# Schematic.net
KiCad netlist of a schematic drawn in EAGLE
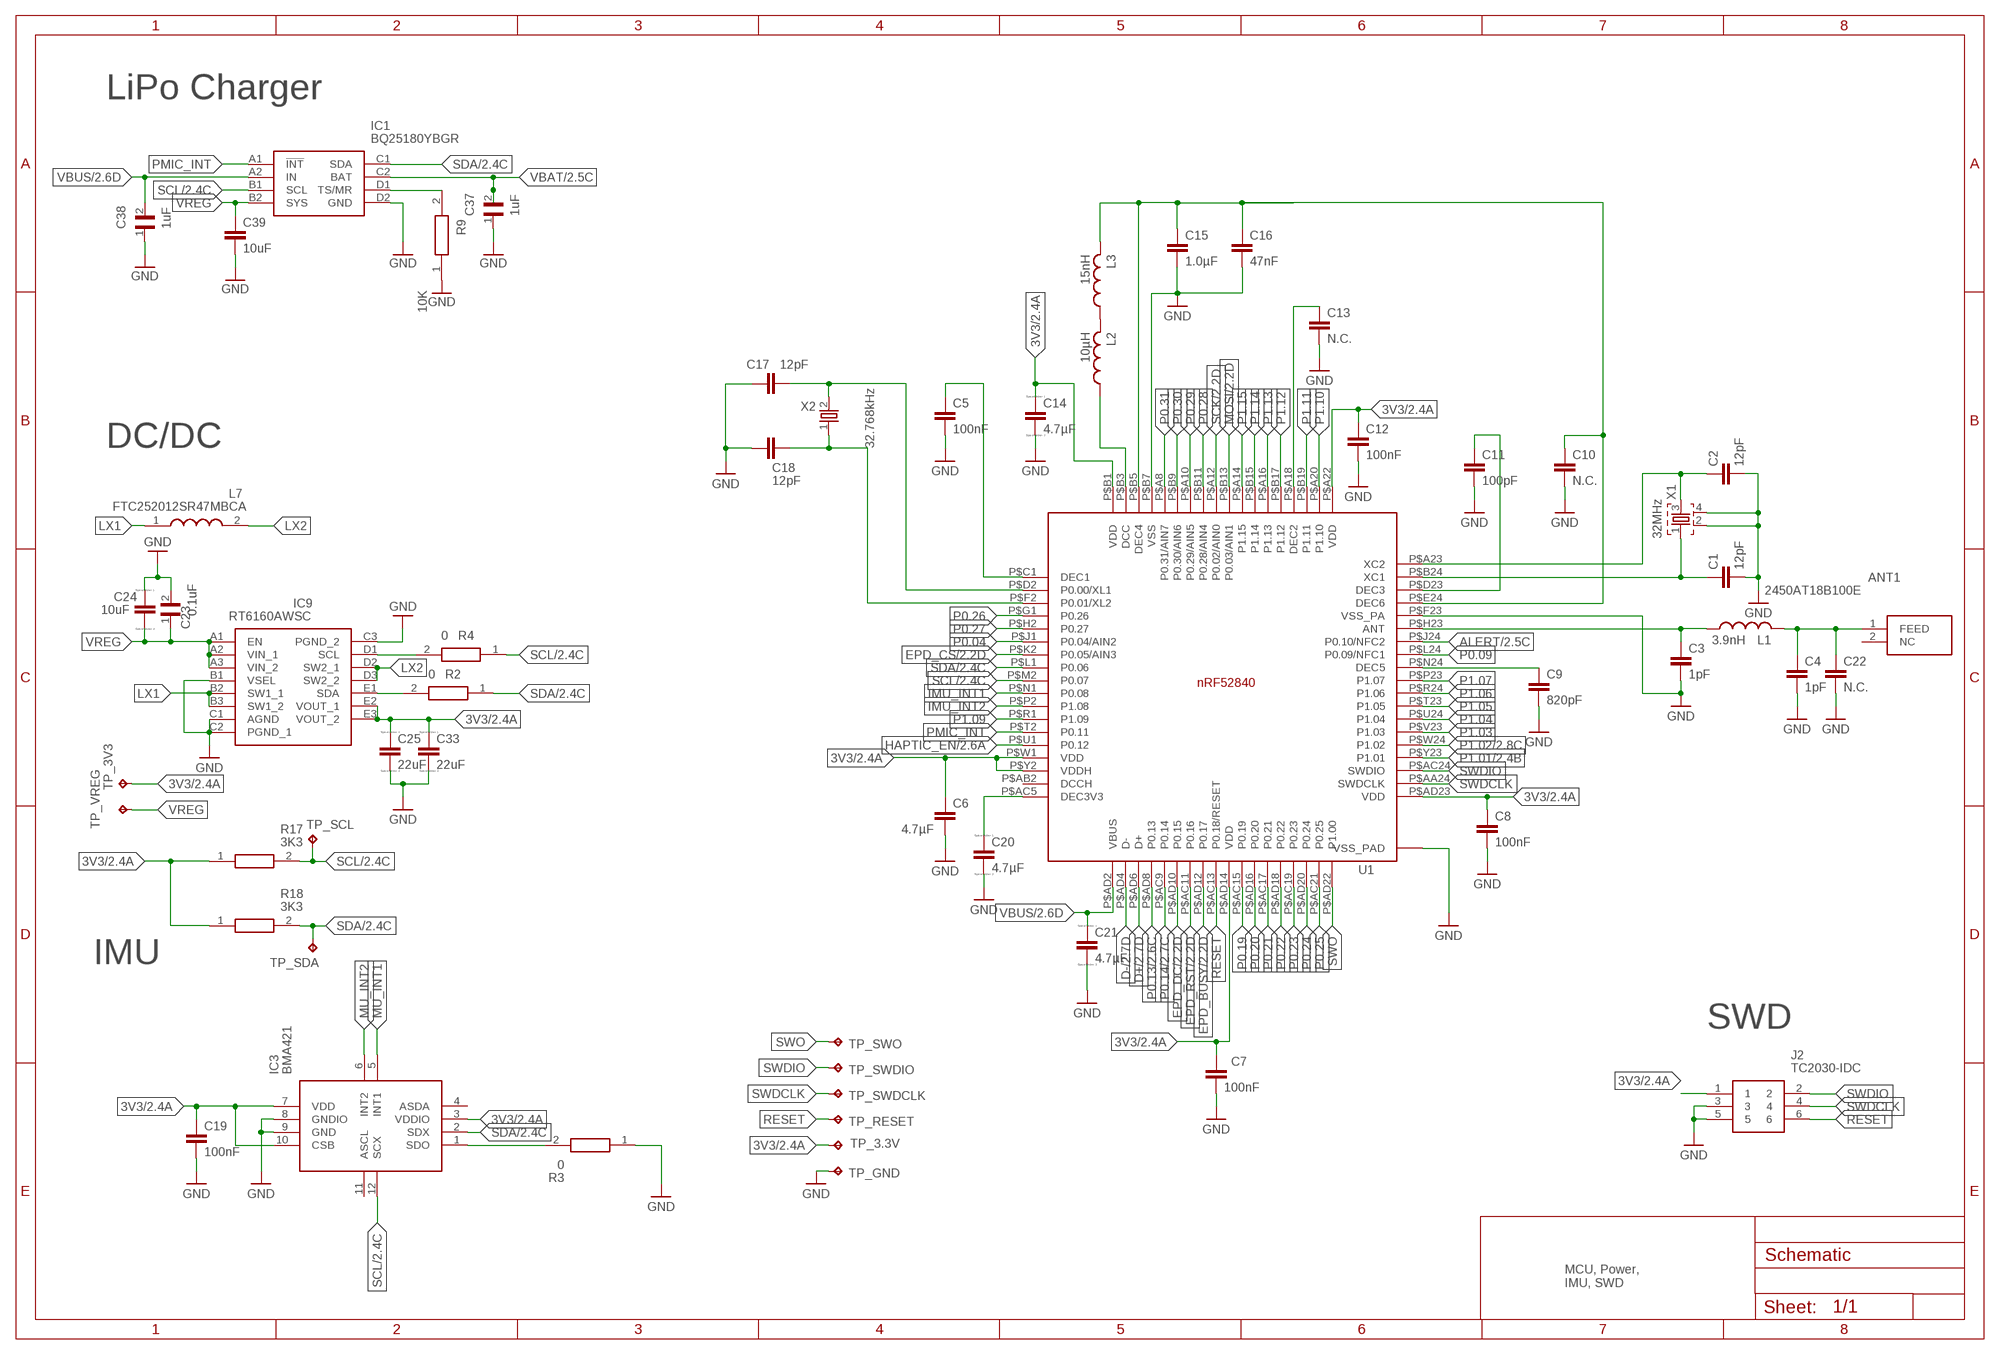
[diagram p0: schematic, sheet 1, part 1 of 2]
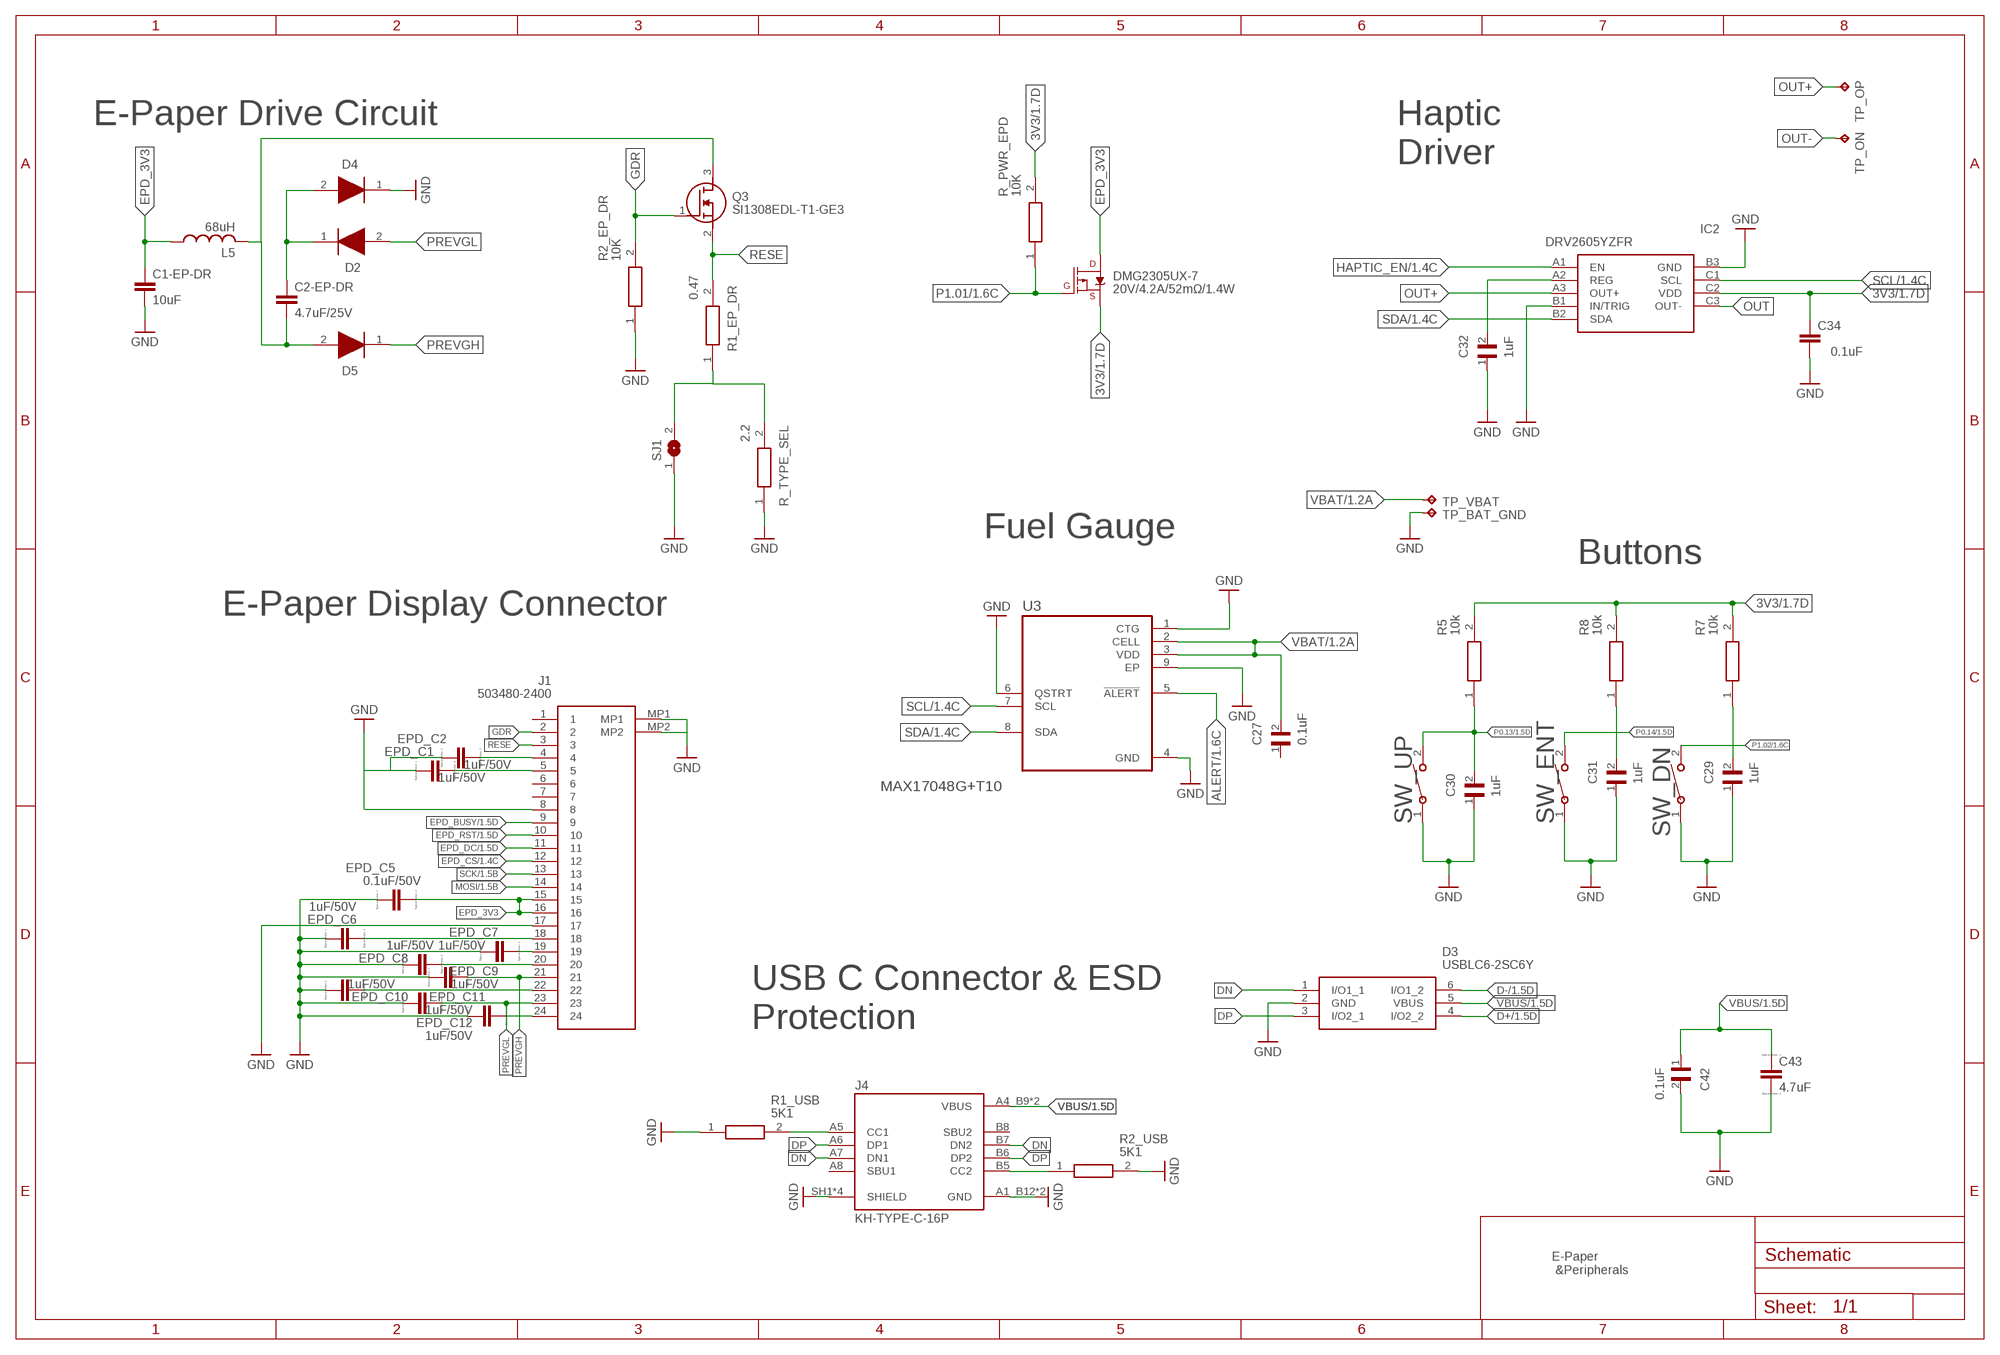
[diagram p1: schematic, sheet 1, part 2 of 2]

(export (version "E")
  (design (tool "Eeschema 10.0.6"))
  (components
    (comp (ref "ANT1")
      (value "2450AT18B100E")
      (footprint "eagle-import:2450AT18B100E_ANTC3216X140N")
      (fields (field (name "MOUSER_PART_NUMBER") "609-2450AT18B100E"))
      (libsource (lib "eagle-import") (part "2450AT18B100E_2450AT18B100E"))
    )
    (comp (ref "C1")
      (value "12pF")
      (footprint "eagle-import:NORDIC_NRF_3_RESC0201_L")
      (libsource (lib "eagle-import") (part "NORDIC_NRF_3_CAPACITOR_0201_L"))
    )
    (comp (ref "C1-EP-DR")
      (value "10uF")
      (footprint "eagle-import:NORDIC_NRF_3_RESC0201_L")
      (libsource (lib "eagle-import") (part "NORDIC_NRF_3_CAPACITOR_0201_L"))
    )
    (comp (ref "C2")
      (value "12pF")
      (footprint "eagle-import:NORDIC_NRF_3_RESC0201_L")
      (libsource (lib "eagle-import") (part "NORDIC_NRF_3_CAPACITOR_0201_L"))
    )
    (comp (ref "C2-EP-DR")
      (value "4.7uF/25V")
      (footprint "eagle-import:NORDIC_NRF_3_RESC0201_L")
      (libsource (lib "eagle-import") (part "NORDIC_NRF_3_CAPACITOR_0201_L"))
    )
    (comp (ref "C3")
      (value "1pF")
      (footprint "eagle-import:NORDIC_NRF_3_RESC0201_L")
      (libsource (lib "eagle-import") (part "NORDIC_NRF_3_CAPACITOR_0201_L"))
    )
    (comp (ref "C4")
      (value "1pF")
      (footprint "eagle-import:NORDIC_NRF_3_RESC0201_L")
      (libsource (lib "eagle-import") (part "NORDIC_NRF_3_CAPACITOR_0201_L"))
    )
    (comp (ref "C5")
      (value "100nF")
      (footprint "eagle-import:NORDIC_NRF_3_RESC0201_L")
      (libsource (lib "eagle-import") (part "NORDIC_NRF_3_CAPACITOR_0201_L"))
    )
    (comp (ref "C6")
      (value "4.7µF")
      (footprint "eagle-import:NORDIC_NRF_3_RESC0201_L")
      (libsource (lib "eagle-import") (part "NORDIC_NRF_3_CAPACITOR_0201_L"))
    )
    (comp (ref "C7")
      (value "100nF")
      (footprint "eagle-import:NORDIC_NRF_3_RESC0201_L")
      (libsource (lib "eagle-import") (part "NORDIC_NRF_3_CAPACITOR_0201_L"))
    )
    (comp (ref "C8")
      (value "100nF")
      (footprint "eagle-import:NORDIC_NRF_3_RESC0201_L")
      (libsource (lib "eagle-import") (part "NORDIC_NRF_3_CAPACITOR_0201_L"))
    )
    (comp (ref "C9")
      (value "820pF")
      (footprint "eagle-import:NORDIC_NRF_3_RESC0201_L")
      (libsource (lib "eagle-import") (part "NORDIC_NRF_3_CAPACITOR_0201_L"))
    )
    (comp (ref "C10")
      (value "N.C.")
      (footprint "eagle-import:NORDIC_NRF_3_RESC0201_L")
      (libsource (lib "eagle-import") (part "NORDIC_NRF_3_CAPACITOR_0201_L"))
    )
    (comp (ref "C11")
      (value "100pF")
      (footprint "eagle-import:NORDIC_NRF_3_RESC0201_L")
      (libsource (lib "eagle-import") (part "NORDIC_NRF_3_CAPACITOR_0201_L"))
    )
    (comp (ref "C12")
      (value "100nF")
      (footprint "eagle-import:NORDIC_NRF_3_RESC0201_L")
      (libsource (lib "eagle-import") (part "NORDIC_NRF_3_CAPACITOR_0201_L"))
    )
    (comp (ref "C13")
      (value "N.C.")
      (footprint "eagle-import:NORDIC_NRF_3_RESC0201_L")
      (libsource (lib "eagle-import") (part "NORDIC_NRF_3_CAPACITOR_0201_L"))
    )
    (comp (ref "C14")
      (value "4.7µF")
      (footprint "eagle-import:ESP32_C6_LIBRARY_1_ESP32_WROVER_EAGLE-LTSPICE_C0402")
      (libsource (lib "eagle-import") (part "ESP32_C6_LIBRARY_1_ESP32_WROVER_EAGLE-LTSPICE_CC0402"))
    )
    (comp (ref "C15")
      (value "1.0µF")
      (footprint "eagle-import:NORDIC_NRF_3_RESC0201_L")
      (libsource (lib "eagle-import") (part "NORDIC_NRF_3_CAPACITOR_0201_L"))
    )
    (comp (ref "C16")
      (value "47nF")
      (footprint "eagle-import:NORDIC_NRF_3_RESC0201_L")
      (libsource (lib "eagle-import") (part "NORDIC_NRF_3_CAPACITOR_0201_L"))
    )
    (comp (ref "C17")
      (value "12pF")
      (footprint "eagle-import:NORDIC_NRF_3_RESC0201_L")
      (libsource (lib "eagle-import") (part "NORDIC_NRF_3_CAPACITOR_0201_L"))
    )
    (comp (ref "C18")
      (value "12pF")
      (footprint "eagle-import:NORDIC_NRF_3_RESC0201_L")
      (libsource (lib "eagle-import") (part "NORDIC_NRF_3_CAPACITOR_0201_L"))
    )
    (comp (ref "C19")
      (value "100nF")
      (footprint "eagle-import:NORDIC_NRF_3_RESC0201_L")
      (libsource (lib "eagle-import") (part "NORDIC_NRF_3_CAPACITOR_0201_L"))
    )
    (comp (ref "C20")
      (value "4.7µF")
      (footprint "eagle-import:ESP32_C6_LIBRARY_1_ESP32_WROVER_EAGLE-LTSPICE_C0402")
      (libsource (lib "eagle-import") (part "ESP32_C6_LIBRARY_1_ESP32_WROVER_EAGLE-LTSPICE_CC0402"))
    )
    (comp (ref "C21")
      (value "4.7µF")
      (footprint "eagle-import:ESP32_C6_LIBRARY_1_ESP32_WROVER_EAGLE-LTSPICE_C0402")
      (libsource (lib "eagle-import") (part "ESP32_C6_LIBRARY_1_ESP32_WROVER_EAGLE-LTSPICE_CC0402"))
    )
    (comp (ref "C22")
      (value "N.C.")
      (footprint "eagle-import:NORDIC_NRF_3_RESC0201_L")
      (libsource (lib "eagle-import") (part "NORDIC_NRF_3_CAPACITOR_0201_L"))
    )
    (comp (ref "C23")
      (value "0.1uF")
      (footprint "eagle-import:GRM011R60J152KE01L_2_CAPC0201X13N")
      (fields (field (name "MF") "Murata") (field (name "MP") "GRM011R60J152KE01L"))
      (libsource (lib "eagle-import") (part "GRM011R60J152KE01L_2_GRM011R60J152KE01L"))
    )
    (comp (ref "C24")
      (value "10uF")
      (footprint "eagle-import:ESP32_C6_LIBRARY_1_ESP32_WROVER_EAGLE-LTSPICE_C0402")
      (libsource (lib "eagle-import") (part "ESP32_C6_LIBRARY_1_ESP32_WROVER_EAGLE-LTSPICE_CC0402"))
    )
    (comp (ref "C25")
      (value "22uF")
      (footprint "eagle-import:ESP32_C6_LIBRARY_1_ESP32_WROVER_EAGLE-LTSPICE_C0402")
      (libsource (lib "eagle-import") (part "ESP32_C6_LIBRARY_1_ESP32_WROVER_EAGLE-LTSPICE_CC0402"))
    )
    (comp (ref "C27")
      (value "0.1uF")
      (footprint "eagle-import:GRM011R60J152KE01L_2_CAPC0201X13N")
      (fields (field (name "MF") "Murata") (field (name "MP") "GRM011R60J152KE01L"))
      (libsource (lib "eagle-import") (part "GRM011R60J152KE01L_2_GRM011R60J152KE01L"))
    )
    (comp (ref "C29")
      (value "1uF")
      (footprint "eagle-import:GRM011R60J152KE01L_2_CAPC0201X13N")
      (fields (field (name "MF") "Murata") (field (name "MP") "GRM011R60J152KE01L"))
      (libsource (lib "eagle-import") (part "GRM011R60J152KE01L_2_GRM011R60J152KE01L"))
    )
    (comp (ref "C30")
      (value "1uF")
      (footprint "eagle-import:GRM011R60J152KE01L_2_CAPC0201X13N")
      (fields (field (name "MF") "Murata") (field (name "MP") "GRM011R60J152KE01L"))
      (libsource (lib "eagle-import") (part "GRM011R60J152KE01L_2_GRM011R60J152KE01L"))
    )
    (comp (ref "C31")
      (value "1uF")
      (footprint "eagle-import:GRM011R60J152KE01L_2_CAPC0201X13N")
      (fields (field (name "MF") "Murata") (field (name "MP") "GRM011R60J152KE01L"))
      (libsource (lib "eagle-import") (part "GRM011R60J152KE01L_2_GRM011R60J152KE01L"))
    )
    (comp (ref "C32")
      (value "1uF")
      (footprint "eagle-import:GRM011R60J152KE01L_2_CAPC0201X13N")
      (fields (field (name "MF") "Murata") (field (name "MP") "GRM011R60J152KE01L"))
      (libsource (lib "eagle-import") (part "GRM011R60J152KE01L_2_GRM011R60J152KE01L"))
    )
    (comp (ref "C33")
      (value "22uF")
      (footprint "eagle-import:ESP32_C6_LIBRARY_1_ESP32_WROVER_EAGLE-LTSPICE_C0402")
      (libsource (lib "eagle-import") (part "ESP32_C6_LIBRARY_1_ESP32_WROVER_EAGLE-LTSPICE_CC0402"))
    )
    (comp (ref "C34")
      (value "0.1uF")
      (footprint "eagle-import:NORDIC_NRF_3_RESC0201_L")
      (libsource (lib "eagle-import") (part "NORDIC_NRF_3_CAPACITOR_0201_L"))
    )
    (comp (ref "C37")
      (value "1uF")
      (footprint "eagle-import:GRM011R60J152KE01L_2_CAPC0201X13N")
      (fields (field (name "MF") "Murata") (field (name "MP") "GRM011R60J152KE01L"))
      (libsource (lib "eagle-import") (part "GRM011R60J152KE01L_2_GRM011R60J152KE01L"))
    )
    (comp (ref "C38")
      (value "1uF")
      (footprint "eagle-import:GRM011R60J152KE01L_2_CAPC0201X13N")
      (fields (field (name "MF") "Murata") (field (name "MP") "GRM011R60J152KE01L"))
      (libsource (lib "eagle-import") (part "GRM011R60J152KE01L_2_GRM011R60J152KE01L"))
    )
    (comp (ref "C39")
      (value "10uF")
      (footprint "eagle-import:NORDIC_NRF_3_RESC0201_L")
      (libsource (lib "eagle-import") (part "NORDIC_NRF_3_CAPACITOR_0201_L"))
    )
    (comp (ref "C42")
      (value "0.1uF")
      (footprint "eagle-import:GRM011R60J152KE01L_2_CAPC0201X13N")
      (fields (field (name "MF") "Murata") (field (name "MP") "GRM011R60J152KE01L"))
      (libsource (lib "eagle-import") (part "GRM011R60J152KE01L_2_GRM011R60J152KE01L"))
    )
    (comp (ref "C43")
      (value "4.7uF")
      (footprint "eagle-import:ESP32_C6_LIBRARY_1_ESP32_WROVER_EAGLE-LTSPICE_C0402")
      (libsource (lib "eagle-import") (part "ESP32_C6_LIBRARY_1_ESP32_WROVER_EAGLE-LTSPICE_CC0402"))
    )
    (comp (ref "D2")
      (value "ESP32_C6_LIBRARY_5_MBR0530")
      (footprint "eagle-import:ESP32_C6_LIBRARY_5_SOD3716X135N")
      (fields (field (name "MF") "ON Semiconductor") (field (name "MP") "MBR0530"))
      (libsource (lib "eagle-import") (part "ESP32_C6_LIBRARY_5_MBR0530"))
    )
    (comp (ref "D3")
      (value "USBLC6-2SC6Y")
      (footprint "eagle-import:ESP32_C6_LIBRARY_3_SOT95P280X145-6N")
      (fields (field (name "MF") "STMicroelectronics"))
      (libsource (lib "eagle-import") (part "ESP32_C6_LIBRARY_3_USBLC6-2SC6Y"))
    )
    (comp (ref "D4")
      (value "ESP32_C6_LIBRARY_5_MBR0530")
      (footprint "eagle-import:ESP32_C6_LIBRARY_5_SOD3716X135N")
      (fields (field (name "MF") "ON Semiconductor") (field (name "MP") "MBR0530"))
      (libsource (lib "eagle-import") (part "ESP32_C6_LIBRARY_5_MBR0530"))
    )
    (comp (ref "D5")
      (value "ESP32_C6_LIBRARY_5_MBR0530")
      (footprint "eagle-import:ESP32_C6_LIBRARY_5_SOD3716X135N")
      (fields (field (name "MF") "ON Semiconductor") (field (name "MP") "MBR0530"))
      (libsource (lib "eagle-import") (part "ESP32_C6_LIBRARY_5_MBR0530"))
    )
    (comp (ref "DMG2305UX-7")
      (value "20V/4.2A/52mΩ/1.4W")
      (footprint "eagle-import:ESP32_C6_LIBRARY_4_ESP32_C6_LIBRARY_4_ESP32_C6_LIBRARY_4_ESP32_C6_LIBRARY_4_ESP32_WROVER_SPARKFUN-DISCRETESEMI_SOT23-3")
      (libsource (lib "eagle-import") (part "ESP32_C6_LIBRARY_4_ESP32_WROVER_SPARKFUN-DISCRETESEMI_MOSFET_PCH-DMG2305UX-7"))
    )
    (comp (ref "EPD_C1")
      (value "1uF/50V")
      (footprint "eagle-import:ESP32_C6_LIBRARY_1_ESP32_WROVER_EAGLE-LTSPICE_C0402")
      (libsource (lib "eagle-import") (part "ESP32_C6_LIBRARY_1_ESP32_WROVER_EAGLE-LTSPICE_CC0402"))
    )
    (comp (ref "EPD_C2")
      (value "1uF/50V")
      (footprint "eagle-import:ESP32_C6_LIBRARY_1_ESP32_WROVER_EAGLE-LTSPICE_C0402")
      (libsource (lib "eagle-import") (part "ESP32_C6_LIBRARY_1_ESP32_WROVER_EAGLE-LTSPICE_CC0402"))
    )
    (comp (ref "EPD_C5")
      (value "0.1uF/50V")
      (footprint "eagle-import:ESP32_C6_LIBRARY_1_ESP32_WROVER_EAGLE-LTSPICE_C0402")
      (libsource (lib "eagle-import") (part "ESP32_C6_LIBRARY_1_ESP32_WROVER_EAGLE-LTSPICE_CC0402"))
    )
    (comp (ref "EPD_C6")
      (value "1uF/50V")
      (footprint "eagle-import:ESP32_C6_LIBRARY_1_ESP32_WROVER_EAGLE-LTSPICE_C0402")
      (libsource (lib "eagle-import") (part "ESP32_C6_LIBRARY_1_ESP32_WROVER_EAGLE-LTSPICE_CC0402"))
    )
    (comp (ref "EPD_C7")
      (value "1uF/50V")
      (footprint "eagle-import:ESP32_C6_LIBRARY_1_ESP32_WROVER_EAGLE-LTSPICE_C0402")
      (libsource (lib "eagle-import") (part "ESP32_C6_LIBRARY_1_ESP32_WROVER_EAGLE-LTSPICE_CC0402"))
    )
    (comp (ref "EPD_C8")
      (value "1uF/50V")
      (footprint "eagle-import:ESP32_C6_LIBRARY_1_ESP32_WROVER_EAGLE-LTSPICE_C0402")
      (libsource (lib "eagle-import") (part "ESP32_C6_LIBRARY_1_ESP32_WROVER_EAGLE-LTSPICE_CC0402"))
    )
    (comp (ref "EPD_C9")
      (value "1uF/50V")
      (footprint "eagle-import:ESP32_C6_LIBRARY_1_ESP32_WROVER_EAGLE-LTSPICE_C0402")
      (libsource (lib "eagle-import") (part "ESP32_C6_LIBRARY_1_ESP32_WROVER_EAGLE-LTSPICE_CC0402"))
    )
    (comp (ref "EPD_C10")
      (value "1uF/50V")
      (footprint "eagle-import:ESP32_C6_LIBRARY_1_ESP32_WROVER_EAGLE-LTSPICE_C0402")
      (libsource (lib "eagle-import") (part "ESP32_C6_LIBRARY_1_ESP32_WROVER_EAGLE-LTSPICE_CC0402"))
    )
    (comp (ref "EPD_C11")
      (value "1uF/50V")
      (footprint "eagle-import:ESP32_C6_LIBRARY_1_ESP32_WROVER_EAGLE-LTSPICE_C0402")
      (libsource (lib "eagle-import") (part "ESP32_C6_LIBRARY_1_ESP32_WROVER_EAGLE-LTSPICE_CC0402"))
    )
    (comp (ref "EPD_C12")
      (value "1uF/50V")
      (footprint "eagle-import:ESP32_C6_LIBRARY_1_ESP32_WROVER_EAGLE-LTSPICE_C0402")
      (libsource (lib "eagle-import") (part "ESP32_C6_LIBRARY_1_ESP32_WROVER_EAGLE-LTSPICE_CC0402"))
    )
    (comp (ref "IC1")
      (value "BQ25180YBGR")
      (footprint "eagle-import:BQ25180YBGR_BGA8C40P2X4_100X155X50")
      (fields (field (name "MOUSER_PART_NUMBER") "595-BQ25180YBGR"))
      (libsource (lib "eagle-import") (part "BQ25180YBGR_BQ25180YBGR"))
    )
    (comp (ref "IC2")
      (value "DRV2605YZFR")
      (footprint "eagle-import:DRV2605YZFR_BGA9C50P3X3_144X144X62")
      (libsource (lib "eagle-import") (part "DRV2605YZFR_DRV2605YZFR"))
    )
    (comp (ref "IC3")
      (value "BMA421")
      (footprint "eagle-import:BMA423_BMA423")
      (fields (field (name "ARROW_PART_NUMBER") "BMA423") (field (name "MOUSER_PART_NUMBER") "262-BMA423"))
      (libsource (lib "eagle-import") (part "BMA423_BMA423"))
    )
    (comp (ref "IC9")
      (value "RT6160AWSC")
      (footprint "eagle-import:RT6160AWSC_BGA15C40P3X5_140X230X60")
      (fields (field (name "MOUSER_PART_NUMBER") "835-RT6160AWSC"))
      (libsource (lib "eagle-import") (part "RT6160AWSC_RT6160AWSC"))
    )
    (comp (ref "J1")
      (value "503480-2400")
      (footprint "eagle-import:503480-2400_5034802400")
      (fields (field (name "MOUSER_PART_NUMBER") "538-503480-2400"))
      (libsource (lib "eagle-import") (part "503480-2400_503480-2400"))
    )
    (comp (ref "J2")
      (value "TC2030-IDC")
      (footprint "eagle-import:TC2030-IDC_TC2030IDC")
      (libsource (lib "eagle-import") (part "TC2030-IDC_TC2030-IDC"))
    )
    (comp (ref "J4")
      (value "KH-TYPE-C-16P")
      (footprint "eagle-import:KH-TYPE-C-16P_KINGHELM_KH-TYPE-C-16P")
      (fields (field (name "MF") "kinghelm"))
      (libsource (lib "eagle-import") (part "KH-TYPE-C-16P_KH-TYPE-C-16P"))
    )
    (comp (ref "L1")
      (value "3.9nH")
      (footprint "eagle-import:NORDIC_NRF_2_RESC0402_L")
      (libsource (lib "eagle-import") (part "NORDIC_NRF_2_INDUCTOR_0402_L"))
    )
    (comp (ref "L2")
      (value "10µH")
      (footprint "eagle-import:NORDIC_NRF_2_RESC0402_L")
      (libsource (lib "eagle-import") (part "NORDIC_NRF_2_INDUCTOR_0402_L"))
    )
    (comp (ref "L3")
      (value "15nH")
      (footprint "eagle-import:NORDIC_NRF_2_RESC0402_L")
      (libsource (lib "eagle-import") (part "NORDIC_NRF_2_INDUCTOR_0402_L"))
    )
    (comp (ref "L5")
      (value "68uH")
      (footprint "eagle-import:NORDIC_NRF_2_RESC0402_L")
      (libsource (lib "eagle-import") (part "NORDIC_NRF_2_INDUCTOR_0402_L"))
    )
    (comp (ref "L7")
      (value "FTC252012SR47MBCA")
      (footprint "eagle-import:MLP2016SR47MT0S1_INDC2016X100N")
      (libsource (lib "eagle-import") (part "MLP2016SR47MT0S1_FTC252012SR47MBCA"))
    )
    (comp (ref "Q3")
      (value "SI1308EDL-T1-GE3")
      (footprint "eagle-import:ESP32_C6_LIBRARY_6_SOT65P210X110-3N")
      (fields (field (name "MF") "Vishay Siliconix"))
      (libsource (lib "eagle-import") (part "ESP32_C6_LIBRARY_6_SI1308EDL-T1-GE3"))
    )
    (comp (ref "R1_EP_DR")
      (value "0.47")
      (footprint "eagle-import:ERA-1AEB3401C_0201")
      (libsource (lib "eagle-import") (part "ERA-1AEB3401C_CPF0201D7K68C1"))
    )
    (comp (ref "R1_USB")
      (value "5K1")
      (footprint "eagle-import:CPF0201D7K68C1_0201")
      (libsource (lib "eagle-import") (part "CPF0201D7K68C1_CPF0201D7K68C1"))
    )
    (comp (ref "R2")
      (value "0")
      (footprint "eagle-import:CPF0201D7K68C1_0201")
      (libsource (lib "eagle-import") (part "CPF0201D7K68C1_CPF0201D7K68C1"))
    )
    (comp (ref "R2_EP_DR")
      (value "10K")
      (footprint "eagle-import:ERA-1AEB3401C_0201")
      (libsource (lib "eagle-import") (part "ERA-1AEB3401C_CPF0201D7K68C1"))
    )
    (comp (ref "R2_USB")
      (value "5K1")
      (footprint "eagle-import:ERA-1AEB3401C_0201")
      (libsource (lib "eagle-import") (part "ERA-1AEB3401C_CPF0201D7K68C1"))
    )
    (comp (ref "R3")
      (value "0")
      (footprint "eagle-import:ERA-1AEB3401C_0201")
      (libsource (lib "eagle-import") (part "ERA-1AEB3401C_CPF0201D7K68C1"))
    )
    (comp (ref "R4")
      (value "0")
      (footprint "eagle-import:CPF0201D7K68C1_0201")
      (libsource (lib "eagle-import") (part "CPF0201D7K68C1_CPF0201D7K68C1"))
    )
    (comp (ref "R5")
      (value "10k")
      (footprint "eagle-import:CPF0201D7K68C1_0201")
      (libsource (lib "eagle-import") (part "CPF0201D7K68C1_CPF0201D7K68C1"))
    )
    (comp (ref "R7")
      (value "10k")
      (footprint "eagle-import:CPF0201D7K68C1_0201")
      (libsource (lib "eagle-import") (part "CPF0201D7K68C1_CPF0201D7K68C1"))
    )
    (comp (ref "R8")
      (value "10k")
      (footprint "eagle-import:CPF0201D7K68C1_0201")
      (libsource (lib "eagle-import") (part "CPF0201D7K68C1_CPF0201D7K68C1"))
    )
    (comp (ref "R9")
      (value "10K")
      (footprint "eagle-import:ERA-1AEB3401C_0201")
      (libsource (lib "eagle-import") (part "ERA-1AEB3401C_CPF0201D7K68C1"))
    )
    (comp (ref "R17")
      (value "3K3")
      (footprint "eagle-import:CPF0201D7K68C1_0201")
      (libsource (lib "eagle-import") (part "CPF0201D7K68C1_CPF0201D7K68C1"))
    )
    (comp (ref "R18")
      (value "3K3")
      (footprint "eagle-import:CPF0201D7K68C1_0201")
      (libsource (lib "eagle-import") (part "CPF0201D7K68C1_CPF0201D7K68C1"))
    )
    (comp (ref "R_PWR_EPD")
      (value "10K")
      (footprint "eagle-import:CPF0201D7K68C1_0201")
      (libsource (lib "eagle-import") (part "CPF0201D7K68C1_CPF0201D7K68C1"))
    )
    (comp (ref "R_TYPE_SEL")
      (value "2.2")
      (footprint "eagle-import:ERA-1AEB3401C_0201")
      (libsource (lib "eagle-import") (part "ERA-1AEB3401C_CPF0201D7K68C1"))
    )
    (comp (ref "SJ1")
      (value "ESP32_C6_LIBRARY_7_JUMPER_SJ")
      (footprint "eagle-import:ESP32_C6_LIBRARY_7_JUMPER_SJ")
      (libsource (lib "eagle-import") (part "ESP32_C6_LIBRARY_7_JUMPER_SJ"))
    )
    (comp (ref "SW_DN")
      (value "2025-10-22_07-23-44_LIBRARY_EVP-AKE31ASW_EVP-AKE31A_PAN")
      (footprint "eagle-import:2025-10-22_07-23-44_LIBRARY_SW_EVP-AKE31A_PAN")
      (fields
        (field (name "MANUFACTURER_PART_NUMBER") "EVP-AKE31A")
        (field (name "COPYRIGHT") "Copyright (C) 2025 Ultra Librarian. All rights reserved.")
      )
      (libsource (lib "eagle-import") (part "2025-10-22_07-23-44_LIBRARY_EVP-AKE31ASW_EVP-AKE31A_PAN"))
    )
    (comp (ref "SW_ENT")
      (value "2025-10-22_07-23-44_LIBRARY_EVP-AKE31ASW_EVP-AKE31A_PAN")
      (footprint "eagle-import:2025-10-22_07-23-44_LIBRARY_SW_EVP-AKE31A_PAN")
      (fields
        (field (name "MANUFACTURER_PART_NUMBER") "EVP-AKE31A")
        (field (name "COPYRIGHT") "Copyright (C) 2025 Ultra Librarian. All rights reserved.")
      )
      (libsource (lib "eagle-import") (part "2025-10-22_07-23-44_LIBRARY_EVP-AKE31ASW_EVP-AKE31A_PAN"))
    )
    (comp (ref "SW_UP")
      (value "2025-10-22_07-23-44_LIBRARY_EVP-AKE31ASW_EVP-AKE31A_PAN")
      (footprint "eagle-import:2025-10-22_07-23-44_LIBRARY_SW_EVP-AKE31A_PAN")
      (fields
        (field (name "MANUFACTURER_PART_NUMBER") "EVP-AKE31A")
        (field (name "COPYRIGHT") "Copyright (C) 2025 Ultra Librarian. All rights reserved.")
      )
      (libsource (lib "eagle-import") (part "2025-10-22_07-23-44_LIBRARY_EVP-AKE31ASW_EVP-AKE31A_PAN"))
    )
    (comp (ref "TP_3.3V")
      (value "HECTOR_WATCH_1_TPTP20R")
      (footprint "eagle-import:HECTOR_WATCH_1_TP20R")
      (libsource (lib "eagle-import") (part "HECTOR_WATCH_1_TPTP20R"))
    )
    (comp (ref "TP_3V3")
      (value "HECTOR_WATCH_1_TPTP20R")
      (footprint "eagle-import:HECTOR_WATCH_1_TP20R")
      (libsource (lib "eagle-import") (part "HECTOR_WATCH_1_TPTP20R"))
    )
    (comp (ref "TP_BAT_GND")
      (value "HECTOR_WATCH_1_TPTP20R")
      (footprint "eagle-import:HECTOR_WATCH_1_TP20R")
      (libsource (lib "eagle-import") (part "HECTOR_WATCH_1_TPTP20R"))
    )
    (comp (ref "TP_GND")
      (value "HECTOR_WATCH_1_TPTP20R")
      (footprint "eagle-import:HECTOR_WATCH_1_TP20R")
      (libsource (lib "eagle-import") (part "HECTOR_WATCH_1_TPTP20R"))
    )
    (comp (ref "TP_ON")
      (value "HECTOR_WATCH_1_TPTP20R")
      (footprint "eagle-import:HECTOR_WATCH_1_TP20R")
      (libsource (lib "eagle-import") (part "HECTOR_WATCH_1_TPTP20R"))
    )
    (comp (ref "TP_OP")
      (value "HECTOR_WATCH_1_TPTP20R")
      (footprint "eagle-import:HECTOR_WATCH_1_TP20R")
      (libsource (lib "eagle-import") (part "HECTOR_WATCH_1_TPTP20R"))
    )
    (comp (ref "TP_RESET")
      (value "HECTOR_WATCH_1_TPTP20R")
      (footprint "eagle-import:HECTOR_WATCH_1_TP20R")
      (libsource (lib "eagle-import") (part "HECTOR_WATCH_1_TPTP20R"))
    )
    (comp (ref "TP_SCL")
      (value "HECTOR_WATCH_1_TPTP20R")
      (footprint "eagle-import:HECTOR_WATCH_1_TP20R")
      (libsource (lib "eagle-import") (part "HECTOR_WATCH_1_TPTP20R"))
    )
    (comp (ref "TP_SDA")
      (value "HECTOR_WATCH_1_TPTP20R")
      (footprint "eagle-import:HECTOR_WATCH_1_TP20R")
      (libsource (lib "eagle-import") (part "HECTOR_WATCH_1_TPTP20R"))
    )
    (comp (ref "TP_SWDCLK")
      (value "HECTOR_WATCH_1_TPTP20R")
      (footprint "eagle-import:HECTOR_WATCH_1_TP20R")
      (libsource (lib "eagle-import") (part "HECTOR_WATCH_1_TPTP20R"))
    )
    (comp (ref "TP_SWDIO")
      (value "HECTOR_WATCH_1_TPTP20R")
      (footprint "eagle-import:HECTOR_WATCH_1_TP20R")
      (libsource (lib "eagle-import") (part "HECTOR_WATCH_1_TPTP20R"))
    )
    (comp (ref "TP_SWO")
      (value "HECTOR_WATCH_1_TPTP20R")
      (footprint "eagle-import:HECTOR_WATCH_1_TP20R")
      (libsource (lib "eagle-import") (part "HECTOR_WATCH_1_TPTP20R"))
    )
    (comp (ref "TP_VBAT")
      (value "HECTOR_WATCH_1_TPTP20R")
      (footprint "eagle-import:HECTOR_WATCH_1_TP20R")
      (libsource (lib "eagle-import") (part "HECTOR_WATCH_1_TPTP20R"))
    )
    (comp (ref "TP_VREG")
      (value "HECTOR_WATCH_1_TPTP20R")
      (footprint "eagle-import:HECTOR_WATCH_1_TP20R")
      (libsource (lib "eagle-import") (part "HECTOR_WATCH_1_TPTP20R"))
    )
    (comp (ref "U1")
      (value "NRF52840_QF")
      (footprint "eagle-import:NORDIC_NRF_4_AQFN50P700X700X85_HS-74N")
      (libsource (lib "eagle-import") (part "NORDIC_NRF_4_NRF52840_QF"))
    )
    (comp (ref "U3")
      (value "MAX17048G+T10")
      (footprint "eagle-import:ESP32_C6_LIBRARY_SON50P200X200X80-9N")
      (fields (field (name "MF") "Analog Devices"))
      (libsource (lib "eagle-import") (part "ESP32_C6_LIBRARY_MAX17048G+T10"))
    )
    (comp (ref "X1")
      (value "32MHz")
      (footprint "eagle-import:NORDIC_NRF_BT-XTAL_2016_N")
      (libsource (lib "eagle-import") (part "NORDIC_NRF_XTAL_32MHZ"))
    )
    (comp (ref "X2")
      (value "32.768kHz")
      (footprint "eagle-import:NORDIC_NRF_1_XTAL_3215_N")
      (libsource (lib "eagle-import") (part "NORDIC_NRF_1_XTAL_32KHZ"))
    )
  )
  (nets
    (net (code "1") (name "3V3{slash}1.7D") (class "Default")
      (node (ref "C34") (pin "1") (pinfunction "1_1") (pintype "passive"))
      (node (ref "DMG2305UX-7") (pin "2") (pinfunction "S_2") (pintype "bidirectional"))
      (node (ref "IC2") (pin "C2") (pinfunction "VDD_C2") (pintype "bidirectional"))
      (node (ref "R5") (pin "2") (pinfunction "2_2") (pintype "bidirectional"))
      (node (ref "R7") (pin "2") (pinfunction "2_2") (pintype "bidirectional"))
      (node (ref "R8") (pin "2") (pinfunction "2_2") (pintype "bidirectional"))
      (node (ref "R_PWR_EPD") (pin "2") (pinfunction "2_2") (pintype "bidirectional"))
    )
    (net (code "2") (name "3V3{slash}2.4A") (class "Default")
      (node (ref "C12") (pin "1") (pinfunction "1_1") (pintype "passive"))
      (node (ref "C14") (pin "1") (pinfunction "1_1") (pintype "passive"))
      (node (ref "C19") (pin "1") (pinfunction "1_1") (pintype "passive"))
      (node (ref "C25") (pin "1") (pinfunction "1_1") (pintype "passive"))
      (node (ref "C33") (pin "1") (pinfunction "1_1") (pintype "passive"))
      (node (ref "C6") (pin "1") (pinfunction "1_1") (pintype "passive"))
      (node (ref "C7") (pin "1") (pinfunction "1_1") (pintype "passive"))
      (node (ref "C8") (pin "1") (pinfunction "1_1") (pintype "passive"))
      (node (ref "IC3") (pin "10") (pinfunction "CSB_10") (pintype "bidirectional"))
      (node (ref "IC3") (pin "3") (pinfunction "VDDIO_3") (pintype "bidirectional"))
      (node (ref "IC3") (pin "7") (pinfunction "VDD_7") (pintype "bidirectional"))
      (node (ref "IC9") (pin "E2") (pinfunction "VOUT_1_E2") (pintype "bidirectional"))
      (node (ref "IC9") (pin "E3") (pinfunction "VOUT_2_E3") (pintype "bidirectional"))
      (node (ref "J2") (pin "1") (pinfunction "1_1") (pintype "bidirectional"))
      (node (ref "R17") (pin "1") (pinfunction "1_1") (pintype "bidirectional"))
      (node (ref "R18") (pin "1") (pinfunction "1_1") (pintype "bidirectional"))
      (node (ref "TP_3.3V") (pin "TP") (pinfunction "TP_TP") (pintype "input"))
      (node (ref "TP_3V3") (pin "TP") (pinfunction "TP_TP") (pintype "input"))
      (node (ref "U1") (pin "P$A22") (pinfunction "VDD_P$A22") (pintype "power_in"))
      (node (ref "U1") (pin "P$AD14") (pinfunction "VDD_P$AD14") (pintype "power_in"))
      (node (ref "U1") (pin "P$AD23") (pinfunction "VDD_P$AD23") (pintype "power_in"))
      (node (ref "U1") (pin "P$B1") (pinfunction "VDD_P$B1") (pintype "power_in"))
      (node (ref "U1") (pin "P$W1") (pinfunction "VDD_P$W1") (pintype "power_in"))
      (node (ref "U1") (pin "P$Y2") (pinfunction "VDDH_P$Y2") (pintype "power_in"))
    )
    (net (code "3") (name "ALERT{slash}1.6C") (class "Default")
      (node (ref "U3") (pin "5") (pinfunction "~{ALERT}_5") (pintype "output"))
    )
    (net (code "4") (name "ALERT{slash}2.5C") (class "Default")
      (node (ref "U1") (pin "P$J24") (pinfunction "P0.10/NFC2_P$J24") (pintype "bidirectional"))
    )
    (net (code "5") (name "D+{slash}1.5D") (class "Default")
      (node (ref "D3") (pin "4") (pinfunction "I/O2_2_4") (pintype "bidirectional"))
    )
    (net (code "6") (name "D+{slash}2.7D") (class "Default")
      (node (ref "U1") (pin "P$AD6") (pinfunction "D+_P$AD6") (pintype "bidirectional"))
    )
    (net (code "7") (name "D-{slash}1.5D") (class "Default")
      (node (ref "D3") (pin "6") (pinfunction "I/O1_2_6") (pintype "bidirectional"))
    )
    (net (code "8") (name "D-{slash}2.7D") (class "Default")
      (node (ref "U1") (pin "P$AD4") (pinfunction "D-_P$AD4") (pintype "bidirectional"))
    )
    (net (code "9") (name "DN") (class "Default")
      (node (ref "D3") (pin "1") (pinfunction "I/O1_1_1") (pintype "bidirectional"))
      (node (ref "J4") (pin "A7") (pinfunction "DN1_A7") (pintype "bidirectional"))
      (node (ref "J4") (pin "B7") (pinfunction "DN2_B7") (pintype "bidirectional"))
    )
    (net (code "10") (name "DP") (class "Default")
      (node (ref "D3") (pin "3") (pinfunction "I/O2_1_3") (pintype "bidirectional"))
      (node (ref "J4") (pin "A6") (pinfunction "DP1_A6") (pintype "bidirectional"))
      (node (ref "J4") (pin "B6") (pinfunction "DP2_B6") (pintype "bidirectional"))
    )
    (net (code "11") (name "EPD_3V3") (class "Default")
      (node (ref "C1-EP-DR") (pin "1") (pinfunction "1_1") (pintype "passive"))
      (node (ref "DMG2305UX-7") (pin "3") (pinfunction "D_3") (pintype "bidirectional"))
      (node (ref "EPD_C5") (pin "2") (pinfunction "2_2") (pintype "passive"))
      (node (ref "J1") (pin "15") (pinfunction "15_15") (pintype "bidirectional"))
      (node (ref "J1") (pin "16") (pinfunction "16_16") (pintype "bidirectional"))
      (node (ref "L5") (pin "1") (pinfunction "1_1") (pintype "passive"))
    )
    (net (code "12") (name "EPD_BUSY{slash}1.5D") (class "Default")
      (node (ref "J1") (pin "9") (pinfunction "9_9") (pintype "bidirectional"))
    )
    (net (code "13") (name "EPD_BUSY{slash}2.2D") (class "Default")
      (node (ref "U1") (pin "P$AD12") (pinfunction "P0.17_P$AD12") (pintype "bidirectional"))
    )
    (net (code "14") (name "EPD_CS{slash}1.4C") (class "Default")
      (node (ref "J1") (pin "12") (pinfunction "12_12") (pintype "bidirectional"))
    )
    (net (code "15") (name "EPD_CS{slash}2.2D") (class "Default")
      (node (ref "U1") (pin "P$K2") (pinfunction "P0.05/AIN3_P$K2") (pintype "bidirectional"))
    )
    (net (code "16") (name "EPD_DC{slash}1.5D") (class "Default")
      (node (ref "J1") (pin "11") (pinfunction "11_11") (pintype "bidirectional"))
    )
    (net (code "17") (name "EPD_DC{slash}2.2D") (class "Default")
      (node (ref "U1") (pin "P$AD10") (pinfunction "P0.15_P$AD10") (pintype "bidirectional"))
    )
    (net (code "18") (name "EPD_RST{slash}1.5D") (class "Default")
      (node (ref "J1") (pin "10") (pinfunction "10_10") (pintype "bidirectional"))
    )
    (net (code "19") (name "EPD_RST{slash}2.2D") (class "Default")
      (node (ref "U1") (pin "P$AC11") (pinfunction "P0.16_P$AC11") (pintype "bidirectional"))
    )
    (net (code "20") (name "GDR") (class "Default")
      (node (ref "J1") (pin "2") (pinfunction "2_2") (pintype "bidirectional"))
      (node (ref "Q3") (pin "1") (pinfunction "G_1") (pintype "bidirectional"))
      (node (ref "R2_EP_DR") (pin "2") (pinfunction "2_2") (pintype "bidirectional"))
    )
    (net (code "21") (name "GND") (class "Default")
      (node (ref "C1") (pin "2") (pinfunction "2_2") (pintype "passive"))
      (node (ref "C1-EP-DR") (pin "2") (pinfunction "2_2") (pintype "passive"))
      (node (ref "C10") (pin "2") (pinfunction "2_2") (pintype "passive"))
      (node (ref "C11") (pin "2") (pinfunction "2_2") (pintype "passive"))
      (node (ref "C12") (pin "2") (pinfunction "2_2") (pintype "passive"))
      (node (ref "C13") (pin "2") (pinfunction "2_2") (pintype "passive"))
      (node (ref "C14") (pin "2") (pinfunction "2_2") (pintype "passive"))
      (node (ref "C15") (pin "2") (pinfunction "2_2") (pintype "passive"))
      (node (ref "C16") (pin "2") (pinfunction "2_2") (pintype "passive"))
      (node (ref "C17") (pin "1") (pinfunction "1_1") (pintype "passive"))
      (node (ref "C18") (pin "2") (pinfunction "2_2") (pintype "passive"))
      (node (ref "C19") (pin "2") (pinfunction "2_2") (pintype "passive"))
      (node (ref "C2") (pin "2") (pinfunction "2_2") (pintype "passive"))
      (node (ref "C20") (pin "2") (pinfunction "2_2") (pintype "passive"))
      (node (ref "C21") (pin "2") (pinfunction "2_2") (pintype "passive"))
      (node (ref "C22") (pin "2") (pinfunction "2_2") (pintype "passive"))
      (node (ref "C23") (pin "2") (pinfunction "2_2") (pintype "passive"))
      (node (ref "C24") (pin "1") (pinfunction "1_1") (pintype "passive"))
      (node (ref "C25") (pin "2") (pinfunction "2_2") (pintype "passive"))
      (node (ref "C29") (pin "1") (pinfunction "1_1") (pintype "passive"))
      (node (ref "C3") (pin "2") (pinfunction "2_2") (pintype "passive"))
      (node (ref "C30") (pin "1") (pinfunction "1_1") (pintype "passive"))
      (node (ref "C31") (pin "1") (pinfunction "1_1") (pintype "passive"))
      (node (ref "C32") (pin "1") (pinfunction "1_1") (pintype "passive"))
      (node (ref "C33") (pin "2") (pinfunction "2_2") (pintype "passive"))
      (node (ref "C34") (pin "2") (pinfunction "2_2") (pintype "passive"))
      (node (ref "C37") (pin "1") (pinfunction "1_1") (pintype "passive"))
      (node (ref "C38") (pin "1") (pinfunction "1_1") (pintype "passive"))
      (node (ref "C39") (pin "2") (pinfunction "2_2") (pintype "passive"))
      (node (ref "C4") (pin "2") (pinfunction "2_2") (pintype "passive"))
      (node (ref "C42") (pin "2") (pinfunction "2_2") (pintype "passive"))
      (node (ref "C43") (pin "2") (pinfunction "2_2") (pintype "passive"))
      (node (ref "C5") (pin "2") (pinfunction "2_2") (pintype "passive"))
      (node (ref "C6") (pin "2") (pinfunction "2_2") (pintype "passive"))
      (node (ref "C7") (pin "2") (pinfunction "2_2") (pintype "passive"))
      (node (ref "C8") (pin "2") (pinfunction "2_2") (pintype "passive"))
      (node (ref "C9") (pin "2") (pinfunction "2_2") (pintype "passive"))
      (node (ref "D3") (pin "2") (pinfunction "GND_2") (pintype "bidirectional"))
      (node (ref "D4") (pin "1") (pinfunction "K_1") (pintype "bidirectional"))
      (node (ref "EPD_C10") (pin "1") (pinfunction "1_1") (pintype "passive"))
      (node (ref "EPD_C11") (pin "1") (pinfunction "1_1") (pintype "passive"))
      (node (ref "EPD_C12") (pin "1") (pinfunction "1_1") (pintype "passive"))
      (node (ref "EPD_C5") (pin "1") (pinfunction "1_1") (pintype "passive"))
      (node (ref "EPD_C6") (pin "1") (pinfunction "1_1") (pintype "passive"))
      (node (ref "EPD_C7") (pin "1") (pinfunction "1_1") (pintype "passive"))
      (node (ref "EPD_C8") (pin "1") (pinfunction "1_1") (pintype "passive"))
      (node (ref "EPD_C9") (pin "1") (pinfunction "1_1") (pintype "passive"))
      (node (ref "IC1") (pin "D2") (pinfunction "GND_D2") (pintype "bidirectional"))
      (node (ref "IC2") (pin "B1") (pinfunction "IN/TRIG_B1") (pintype "bidirectional"))
      (node (ref "IC2") (pin "B3") (pinfunction "GND_B3") (pintype "bidirectional"))
      (node (ref "IC3") (pin "8") (pinfunction "GNDIO_8") (pintype "bidirectional"))
      (node (ref "IC3") (pin "9") (pinfunction "GND_9") (pintype "bidirectional"))
      (node (ref "IC9") (pin "B1") (pinfunction "VSEL_B1") (pintype "bidirectional"))
      (node (ref "IC9") (pin "C1") (pinfunction "AGND_C1") (pintype "bidirectional"))
      (node (ref "IC9") (pin "C2") (pinfunction "PGND_1_C2") (pintype "bidirectional"))
      (node (ref "IC9") (pin "C3") (pinfunction "PGND_2_C3") (pintype "bidirectional"))
      (node (ref "J1") (pin "17") (pinfunction "17_17") (pintype "bidirectional"))
      (node (ref "J1") (pin "8") (pinfunction "8_8") (pintype "bidirectional"))
      (node (ref "J1") (pin "MP1") (pinfunction "MP1_MP1") (pintype "bidirectional"))
      (node (ref "J2") (pin "3") (pinfunction "3_3") (pintype "bidirectional"))
      (node (ref "J2") (pin "5") (pinfunction "5_5") (pintype "bidirectional"))
      (node (ref "J4") (pin "A12_B1") (pinfunction "GND_A12_B1") (pintype "power_in"))
      (node (ref "J4") (pin "A1_B12") (pinfunction "GND_A1_B12") (pintype "power_in"))
      (node (ref "J4") (pin "SH1") (pinfunction "SHIELD_SH1") (pintype "passive"))
      (node (ref "J4") (pin "SH2") (pinfunction "SHIELD_SH2") (pintype "passive"))
      (node (ref "J4") (pin "SH3") (pinfunction "SHIELD_SH3") (pintype "passive"))
      (node (ref "J4") (pin "SH4") (pinfunction "SHIELD_SH4") (pintype "passive"))
      (node (ref "R1_USB") (pin "1") (pinfunction "1_1") (pintype "bidirectional"))
      (node (ref "R2_EP_DR") (pin "1") (pinfunction "1_1") (pintype "bidirectional"))
      (node (ref "R2_USB") (pin "2") (pinfunction "2_2") (pintype "bidirectional"))
      (node (ref "R3") (pin "1") (pinfunction "1_1") (pintype "bidirectional"))
      (node (ref "R9") (pin "1") (pinfunction "1_1") (pintype "bidirectional"))
      (node (ref "R_TYPE_SEL") (pin "1") (pinfunction "1_1") (pintype "bidirectional"))
      (node (ref "SJ1") (pin "1") (pinfunction "1_1") (pintype "passive"))
      (node (ref "SW_DN") (pin "1") (pinfunction "1_1") (pintype "passive"))
      (node (ref "SW_ENT") (pin "1") (pinfunction "1_1") (pintype "passive"))
      (node (ref "SW_UP") (pin "1") (pinfunction "1_1") (pintype "passive"))
      (node (ref "TP_BAT_GND") (pin "TP") (pinfunction "TP_TP") (pintype "input"))
      (node (ref "TP_GND") (pin "TP") (pinfunction "TP_TP") (pintype "input"))
      (node (ref "U1") (pin "P$74") (pinfunction "VSS_PAD_P$74") (pintype "bidirectional"))
      (node (ref "U1") (pin "P$75") (pinfunction "VSS_PAD_P$75") (pintype "bidirectional"))
      (node (ref "U1") (pin "P$76") (pinfunction "VSS_PAD_P$76") (pintype "bidirectional"))
      (node (ref "U1") (pin "P$77") (pinfunction "VSS_PAD_P$77") (pintype "bidirectional"))
      (node (ref "U1") (pin "P$78") (pinfunction "VSS_PAD_P$78") (pintype "bidirectional"))
      (node (ref "U1") (pin "P$79") (pinfunction "VSS_PAD_P$79") (pintype "bidirectional"))
      (node (ref "U1") (pin "P$80") (pinfunction "VSS_PAD_P$80") (pintype "bidirectional"))
      (node (ref "U1") (pin "P$81") (pinfunction "VSS_PAD_P$81") (pintype "bidirectional"))
      (node (ref "U1") (pin "P$82") (pinfunction "VSS_PAD_P$82") (pintype "bidirectional"))
      (node (ref "U1") (pin "P$83") (pinfunction "VSS_PAD_P$83") (pintype "bidirectional"))
      (node (ref "U1") (pin "P$84") (pinfunction "VSS_PAD_P$84") (pintype "bidirectional"))
      (node (ref "U1") (pin "P$85") (pinfunction "VSS_PAD_P$85") (pintype "bidirectional"))
      (node (ref "U1") (pin "P$86") (pinfunction "VSS_PAD_P$86") (pintype "bidirectional"))
      (node (ref "U1") (pin "P$87") (pinfunction "VSS_PAD_P$87") (pintype "bidirectional"))
      (node (ref "U1") (pin "P$88") (pinfunction "VSS_PAD_P$88") (pintype "bidirectional"))
      (node (ref "U1") (pin "P$89") (pinfunction "VSS_PAD_P$89") (pintype "bidirectional"))
      (node (ref "U1") (pin "P$90") (pinfunction "VSS_PAD_P$90") (pintype "bidirectional"))
      (node (ref "U1") (pin "P$B7") (pinfunction "VSS_P$B7") (pintype "power_in"))
      (node (ref "U1") (pin "P$F23") (pinfunction "VSS_PA_P$F23") (pintype "bidirectional"))
      (node (ref "U3") (pin "1") (pinfunction "CTG_1") (pintype "power_in"))
      (node (ref "U3") (pin "4") (pinfunction "GND_4") (pintype "power_in"))
      (node (ref "U3") (pin "6") (pinfunction "QSTRT_6") (pintype "input"))
      (node (ref "U3") (pin "9") (pinfunction "EP_9") (pintype "power_in"))
      (node (ref "X1") (pin "2") (pinfunction "2_2") (pintype "passive"))
      (node (ref "X1") (pin "4") (pinfunction "4_4") (pintype "passive"))
    )
    (net (code "22") (name "HAPTIC_EN{slash}1.4C") (class "Default")
      (node (ref "IC2") (pin "A1") (pinfunction "EN_A1") (pintype "bidirectional"))
    )
    (net (code "23") (name "HAPTIC_EN{slash}2.6A") (class "Default")
      (node (ref "U1") (pin "P$U1") (pinfunction "P0.12_P$U1") (pintype "bidirectional"))
    )
    (net (code "24") (name "IMU_INT1") (class "Default")
      (node (ref "U1") (pin "P$N1") (pinfunction "P0.08_P$N1") (pintype "bidirectional"))
    )
    (net (code "25") (name "IMU_INT2") (class "Default")
      (node (ref "U1") (pin "P$P2") (pinfunction "P1.08_P$P2") (pintype "bidirectional"))
    )
    (net (code "26") (name "LX1") (class "Default")
      (node (ref "IC9") (pin "B2") (pinfunction "SW1_1_B2") (pintype "bidirectional"))
      (node (ref "IC9") (pin "B3") (pinfunction "SW1_2_B3") (pintype "bidirectional"))
      (node (ref "L7") (pin "1") (pinfunction "1_1") (pintype "bidirectional"))
    )
    (net (code "27") (name "LX2") (class "Default")
      (node (ref "IC9") (pin "D2") (pinfunction "SW2_1_D2") (pintype "bidirectional"))
      (node (ref "IC9") (pin "D3") (pinfunction "SW2_2_D3") (pintype "bidirectional"))
      (node (ref "L7") (pin "2") (pinfunction "2_2") (pintype "bidirectional"))
    )
    (net (code "28") (name "MOSI{slash}1.5B") (class "Default")
      (node (ref "J1") (pin "14") (pinfunction "14_14") (pintype "bidirectional"))
    )
    (net (code "29") (name "MOSI{slash}2.2D") (class "Default")
      (node (ref "U1") (pin "P$B13") (pinfunction "P0.03/AIN1_P$B13") (pintype "bidirectional"))
    )
    (net (code "30") (name "MU_INT1") (class "Default")
      (node (ref "IC3") (pin "5") (pinfunction "INT1_5") (pintype "bidirectional"))
    )
    (net (code "31") (name "MU_INT2") (class "Default")
      (node (ref "IC3") (pin "6") (pinfunction "INT2_6") (pintype "bidirectional"))
    )
    (net (code "32") (name "Net-(ANT1-FEED)") (class "Default")
      (node (ref "ANT1") (pin "1") (pinfunction "FEED_1") (pintype "input"))
      (node (ref "C22") (pin "1") (pinfunction "1_1") (pintype "passive"))
      (node (ref "C4") (pin "1") (pinfunction "1_1") (pintype "passive"))
      (node (ref "L1") (pin "2") (pinfunction "2_2") (pintype "passive"))
    )
    (net (code "33") (name "Net-(C29-Pad2)") (class "Default")
      (node (ref "C29") (pin "2") (pinfunction "2_2") (pintype "passive"))
      (node (ref "R7") (pin "1") (pinfunction "1_1") (pintype "bidirectional"))
    )
    (net (code "34") (name "Net-(C31-Pad2)") (class "Default")
      (node (ref "C31") (pin "2") (pinfunction "2_2") (pintype "passive"))
      (node (ref "R8") (pin "1") (pinfunction "1_1") (pintype "bidirectional"))
    )
    (net (code "35") (name "Net-(D2-K)") (class "Default")
      (node (ref "C2-EP-DR") (pin "1") (pinfunction "1_1") (pintype "passive"))
      (node (ref "D2") (pin "1") (pinfunction "K_1") (pintype "bidirectional"))
      (node (ref "D4") (pin "2") (pinfunction "A_2") (pintype "bidirectional"))
    )
    (net (code "36") (name "Net-(D5-A)") (class "Default")
      (node (ref "C2-EP-DR") (pin "2") (pinfunction "2_2") (pintype "passive"))
      (node (ref "D5") (pin "2") (pinfunction "A_2") (pintype "bidirectional"))
      (node (ref "L5") (pin "2") (pinfunction "2_2") (pintype "passive"))
      (node (ref "Q3") (pin "3") (pinfunction "D_3") (pintype "bidirectional"))
    )
    (net (code "37") (name "Net-(EPD_C1-Pad2)") (class "Default")
      (node (ref "EPD_C1") (pin "2") (pinfunction "2_2") (pintype "passive"))
      (node (ref "J1") (pin "5") (pinfunction "5_5") (pintype "bidirectional"))
    )
    (net (code "38") (name "Net-(EPD_C2-Pad2)") (class "Default")
      (node (ref "EPD_C2") (pin "2") (pinfunction "2_2") (pintype "passive"))
      (node (ref "J1") (pin "4") (pinfunction "4_4") (pintype "bidirectional"))
    )
    (net (code "39") (name "Net-(EPD_C6-Pad2)") (class "Default")
      (node (ref "EPD_C6") (pin "2") (pinfunction "2_2") (pintype "passive"))
      (node (ref "J1") (pin "18") (pinfunction "18_18") (pintype "bidirectional"))
    )
    (net (code "40") (name "Net-(EPD_C7-Pad2)") (class "Default")
      (node (ref "EPD_C7") (pin "2") (pinfunction "2_2") (pintype "passive"))
      (node (ref "J1") (pin "19") (pinfunction "19_19") (pintype "bidirectional"))
    )
    (net (code "41") (name "Net-(EPD_C8-Pad2)") (class "Default")
      (node (ref "EPD_C8") (pin "2") (pinfunction "2_2") (pintype "passive"))
      (node (ref "J1") (pin "20") (pinfunction "20_20") (pintype "bidirectional"))
    )
    (net (code "42") (name "Net-(EPD_C10-Pad2)") (class "Default")
      (node (ref "EPD_C10") (pin "2") (pinfunction "2_2") (pintype "passive"))
      (node (ref "J1") (pin "22") (pinfunction "22_22") (pintype "bidirectional"))
    )
    (net (code "43") (name "Net-(EPD_C12-Pad2)") (class "Default")
      (node (ref "EPD_C12") (pin "2") (pinfunction "2_2") (pintype "passive"))
      (node (ref "J1") (pin "24") (pinfunction "24_24") (pintype "bidirectional"))
    )
    (net (code "44") (name "Net-(IC1-TS{slash}MR)") (class "Default")
      (node (ref "IC1") (pin "D1") (pinfunction "TS/MR_D1") (pintype "bidirectional"))
      (node (ref "R9") (pin "2") (pinfunction "2_2") (pintype "bidirectional"))
    )
    (net (code "45") (name "Net-(IC2-REG)") (class "Default")
      (node (ref "C32") (pin "2") (pinfunction "2_2") (pintype "passive"))
      (node (ref "IC2") (pin "A2") (pinfunction "REG_A2") (pintype "bidirectional"))
    )
    (net (code "46") (name "Net-(IC3-SDO)") (class "Default")
      (node (ref "IC3") (pin "1") (pinfunction "SDO_1") (pintype "bidirectional"))
      (node (ref "R3") (pin "2") (pinfunction "2_2") (pintype "bidirectional"))
    )
    (net (code "47") (name "Net-(IC9-SCL)") (class "Default")
      (node (ref "IC9") (pin "D1") (pinfunction "SCL_D1") (pintype "bidirectional"))
      (node (ref "R4") (pin "2") (pinfunction "2_2") (pintype "bidirectional"))
    )
    (net (code "48") (name "Net-(IC9-SDA)") (class "Default")
      (node (ref "IC9") (pin "E1") (pinfunction "SDA_E1") (pintype "bidirectional"))
      (node (ref "R2") (pin "2") (pinfunction "2_2") (pintype "bidirectional"))
    )
    (net (code "49") (name "Net-(J4-CC1)") (class "Default")
      (node (ref "J4") (pin "A5") (pinfunction "CC1_A5") (pintype "bidirectional"))
      (node (ref "R1_USB") (pin "2") (pinfunction "2_2") (pintype "bidirectional"))
    )
    (net (code "50") (name "Net-(J4-CC2)") (class "Default")
      (node (ref "J4") (pin "B5") (pinfunction "CC2_B5") (pintype "bidirectional"))
      (node (ref "R2_USB") (pin "1") (pinfunction "1_1") (pintype "bidirectional"))
    )
    (net (code "51") (name "Net-(L2-Pad2)") (class "Default")
      (node (ref "L2") (pin "2") (pinfunction "2_2") (pintype "passive"))
      (node (ref "L3") (pin "1") (pinfunction "1_1") (pintype "passive"))
    )
    (net (code "52") (name "Net-(R1_EP_DR-Pad1)") (class "Default")
      (node (ref "R1_EP_DR") (pin "1") (pinfunction "1_1") (pintype "bidirectional"))
      (node (ref "R_TYPE_SEL") (pin "2") (pinfunction "2_2") (pintype "bidirectional"))
      (node (ref "SJ1") (pin "2") (pinfunction "2_2") (pintype "passive"))
    )
    (net (code "53") (name "Net-(U1-ANT)") (class "Default")
      (node (ref "C3") (pin "1") (pinfunction "1_1") (pintype "passive"))
      (node (ref "L1") (pin "1") (pinfunction "1_1") (pintype "passive"))
      (node (ref "U1") (pin "P$H23") (pinfunction "ANT_P$H23") (pintype "bidirectional"))
    )
    (net (code "54") (name "Net-(U1-DCC)") (class "Default")
      (node (ref "L2") (pin "1") (pinfunction "1_1") (pintype "passive"))
      (node (ref "U1") (pin "P$B3") (pinfunction "DCC_P$B3") (pintype "output"))
    )
    (net (code "55") (name "Net-(U1-DEC1)") (class "Default")
      (node (ref "C5") (pin "1") (pinfunction "1_1") (pintype "passive"))
      (node (ref "U1") (pin "P$C1") (pinfunction "DEC1_P$C1") (pintype "power_in"))
    )
    (net (code "56") (name "Net-(U1-DEC2)") (class "Default")
      (node (ref "C13") (pin "1") (pinfunction "1_1") (pintype "passive"))
      (node (ref "U1") (pin "P$A18") (pinfunction "DEC2_P$A18") (pintype "bidirectional"))
    )
    (net (code "57") (name "Net-(U1-DEC3)") (class "Default")
      (node (ref "C11") (pin "1") (pinfunction "1_1") (pintype "passive"))
      (node (ref "U1") (pin "P$D23") (pinfunction "DEC3_P$D23") (pintype "bidirectional"))
    )
    (net (code "58") (name "Net-(U1-DEC3V3)") (class "Default")
      (node (ref "C20") (pin "1") (pinfunction "1_1") (pintype "passive"))
      (node (ref "U1") (pin "P$AC5") (pinfunction "DEC3V3_P$AC5") (pintype "bidirectional"))
    )
    (net (code "59") (name "Net-(U1-DEC4)") (class "Default")
      (node (ref "C10") (pin "1") (pinfunction "1_1") (pintype "passive"))
      (node (ref "C15") (pin "1") (pinfunction "1_1") (pintype "passive"))
      (node (ref "C16") (pin "1") (pinfunction "1_1") (pintype "passive"))
      (node (ref "L3") (pin "2") (pinfunction "2_2") (pintype "passive"))
      (node (ref "U1") (pin "P$B5") (pinfunction "DEC4_P$B5") (pintype "power_in"))
      (node (ref "U1") (pin "P$E24") (pinfunction "DEC6_P$E24") (pintype "bidirectional"))
    )
    (net (code "60") (name "Net-(U1-DEC5)") (class "Default")
      (node (ref "C9") (pin "1") (pinfunction "1_1") (pintype "passive"))
      (node (ref "U1") (pin "P$N24") (pinfunction "DEC5_P$N24") (pintype "bidirectional"))
    )
    (net (code "61") (name "Net-(U1-P0.00{slash}XL1)") (class "Default")
      (node (ref "C17") (pin "2") (pinfunction "2_2") (pintype "passive"))
      (node (ref "U1") (pin "P$D2") (pinfunction "P0.00/XL1_P$D2") (pintype "bidirectional"))
      (node (ref "X2") (pin "2") (pinfunction "2_2") (pintype "passive"))
    )
    (net (code "62") (name "Net-(U1-P0.01{slash}XL2)") (class "Default")
      (node (ref "C18") (pin "1") (pinfunction "1_1") (pintype "passive"))
      (node (ref "U1") (pin "P$F2") (pinfunction "P0.01/XL2_P$F2") (pintype "bidirectional"))
      (node (ref "X2") (pin "1") (pinfunction "1_1") (pintype "passive"))
    )
    (net (code "63") (name "Net-(U1-XC1)") (class "Default")
      (node (ref "C1") (pin "1") (pinfunction "1_1") (pintype "passive"))
      (node (ref "U1") (pin "P$B24") (pinfunction "XC1_P$B24") (pintype "input"))
      (node (ref "X1") (pin "1") (pinfunction "1_1") (pintype "passive"))
    )
    (net (code "64") (name "Net-(U1-XC2)") (class "Default")
      (node (ref "C2") (pin "1") (pinfunction "1_1") (pintype "passive"))
      (node (ref "U1") (pin "P$A23") (pinfunction "XC2_P$A23") (pintype "output"))
      (node (ref "X1") (pin "3") (pinfunction "3_3") (pintype "passive"))
    )
    (net (code "65") (name "OUT") (class "Default")
      (node (ref "IC2") (pin "C3") (pinfunction "OUT-_C3") (pintype "bidirectional"))
    )
    (net (code "66") (name "OUT+") (class "Default")
      (node (ref "IC2") (pin "A3") (pinfunction "OUT+_A3") (pintype "bidirectional"))
      (node (ref "TP_OP") (pin "TP") (pinfunction "TP_TP") (pintype "input"))
    )
    (net (code "67") (name "OUT-") (class "Default")
      (node (ref "TP_ON") (pin "TP") (pinfunction "TP_TP") (pintype "input"))
    )
    (net (code "68") (name "P0.04") (class "Default")
      (node (ref "U1") (pin "P$J1") (pinfunction "P0.04/AIN2_P$J1") (pintype "bidirectional"))
    )
    (net (code "69") (name "P0.09") (class "Default")
      (node (ref "U1") (pin "P$L24") (pinfunction "P0.09/NFC1_P$L24") (pintype "bidirectional"))
    )
    (net (code "70") (name "P0.13{slash}1.5D") (class "Default")
      (node (ref "C30") (pin "2") (pinfunction "2_2") (pintype "passive"))
      (node (ref "R5") (pin "1") (pinfunction "1_1") (pintype "bidirectional"))
      (node (ref "SW_UP") (pin "2") (pinfunction "2_2") (pintype "passive"))
    )
    (net (code "71") (name "P0.13{slash}2.6C") (class "Default")
      (node (ref "U1") (pin "P$AD8") (pinfunction "P0.13_P$AD8") (pintype "bidirectional"))
    )
    (net (code "72") (name "P0.14{slash}1.5D") (class "Default")
      (node (ref "SW_ENT") (pin "2") (pinfunction "2_2") (pintype "passive"))
    )
    (net (code "73") (name "P0.14{slash}2.7C") (class "Default")
      (node (ref "U1") (pin "P$AC9") (pinfunction "P0.14_P$AC9") (pintype "bidirectional"))
    )
    (net (code "74") (name "P0.19") (class "Default")
      (node (ref "U1") (pin "P$AC15") (pinfunction "P0.19_P$AC15") (pintype "bidirectional"))
    )
    (net (code "75") (name "P0.20") (class "Default")
      (node (ref "U1") (pin "P$AD16") (pinfunction "P0.20_P$AD16") (pintype "bidirectional"))
    )
    (net (code "76") (name "P0.21") (class "Default")
      (node (ref "U1") (pin "P$AC17") (pinfunction "P0.21_P$AC17") (pintype "bidirectional"))
    )
    (net (code "77") (name "P0.22") (class "Default")
      (node (ref "U1") (pin "P$AD18") (pinfunction "P0.22_P$AD18") (pintype "bidirectional"))
    )
    (net (code "78") (name "P0.23") (class "Default")
      (node (ref "U1") (pin "P$AC19") (pinfunction "P0.23_P$AC19") (pintype "bidirectional"))
    )
    (net (code "79") (name "P0.24") (class "Default")
      (node (ref "U1") (pin "P$AD20") (pinfunction "P0.24_P$AD20") (pintype "bidirectional"))
    )
    (net (code "80") (name "P0.25") (class "Default")
      (node (ref "U1") (pin "P$AC21") (pinfunction "P0.25_P$AC21") (pintype "bidirectional"))
    )
    (net (code "81") (name "P0.26") (class "Default")
      (node (ref "U1") (pin "P$G1") (pinfunction "P0.26_P$G1") (pintype "bidirectional"))
    )
    (net (code "82") (name "P0.27") (class "Default")
      (node (ref "U1") (pin "P$H2") (pinfunction "P0.27_P$H2") (pintype "bidirectional"))
    )
    (net (code "83") (name "P0.28") (class "Default")
      (node (ref "U1") (pin "P$B11") (pinfunction "P0.28/AIN4_P$B11") (pintype "bidirectional"))
    )
    (net (code "84") (name "P0.29") (class "Default")
      (node (ref "U1") (pin "P$A10") (pinfunction "P0.29/AIN5_P$A10") (pintype "bidirectional"))
    )
    (net (code "85") (name "P0.30") (class "Default")
      (node (ref "U1") (pin "P$B9") (pinfunction "P0.30/AIN6_P$B9") (pintype "bidirectional"))
    )
    (net (code "86") (name "P0.31") (class "Default")
      (node (ref "U1") (pin "P$A8") (pinfunction "P0.31/AIN7_P$A8") (pintype "bidirectional"))
    )
    (net (code "87") (name "P1.01{slash}1.6C") (class "Default")
      (node (ref "DMG2305UX-7") (pin "1") (pinfunction "G_1") (pintype "bidirectional"))
      (node (ref "R_PWR_EPD") (pin "1") (pinfunction "1_1") (pintype "bidirectional"))
    )
    (net (code "88") (name "P1.01{slash}2.4B") (class "Default")
      (node (ref "U1") (pin "P$Y23") (pinfunction "P1.01_P$Y23") (pintype "bidirectional"))
    )
    (net (code "89") (name "P1.02{slash}1.6C") (class "Default")
      (node (ref "SW_DN") (pin "2") (pinfunction "2_2") (pintype "passive"))
    )
    (net (code "90") (name "P1.02{slash}2.8C") (class "Default")
      (node (ref "U1") (pin "P$W24") (pinfunction "P1.02_P$W24") (pintype "bidirectional"))
    )
    (net (code "91") (name "P1.03") (class "Default")
      (node (ref "U1") (pin "P$V23") (pinfunction "P1.03_P$V23") (pintype "bidirectional"))
    )
    (net (code "92") (name "P1.04") (class "Default")
      (node (ref "U1") (pin "P$U24") (pinfunction "P1.04_P$U24") (pintype "bidirectional"))
    )
    (net (code "93") (name "P1.05") (class "Default")
      (node (ref "U1") (pin "P$T23") (pinfunction "P1.05_P$T23") (pintype "bidirectional"))
    )
    (net (code "94") (name "P1.06") (class "Default")
      (node (ref "U1") (pin "P$R24") (pinfunction "P1.06_P$R24") (pintype "bidirectional"))
    )
    (net (code "95") (name "P1.07") (class "Default")
      (node (ref "U1") (pin "P$P23") (pinfunction "P1.07_P$P23") (pintype "bidirectional"))
    )
    (net (code "96") (name "P1.09") (class "Default")
      (node (ref "U1") (pin "P$R1") (pinfunction "P1.09_P$R1") (pintype "bidirectional"))
    )
    (net (code "97") (name "P1.10") (class "Default")
      (node (ref "U1") (pin "P$A20") (pinfunction "P1.10_P$A20") (pintype "bidirectional"))
    )
    (net (code "98") (name "P1.11") (class "Default")
      (node (ref "U1") (pin "P$B19") (pinfunction "P1.11_P$B19") (pintype "bidirectional"))
    )
    (net (code "99") (name "P1.12") (class "Default")
      (node (ref "U1") (pin "P$B17") (pinfunction "P1.12_P$B17") (pintype "bidirectional"))
    )
    (net (code "100") (name "P1.13") (class "Default")
      (node (ref "U1") (pin "P$A16") (pinfunction "P1.13_P$A16") (pintype "bidirectional"))
    )
    (net (code "101") (name "P1.14") (class "Default")
      (node (ref "U1") (pin "P$B15") (pinfunction "P1.14_P$B15") (pintype "bidirectional"))
    )
    (net (code "102") (name "P1.15") (class "Default")
      (node (ref "U1") (pin "P$A14") (pinfunction "P1.15_P$A14") (pintype "bidirectional"))
    )
    (net (code "103") (name "PMIC_INT") (class "Default")
      (node (ref "IC1") (pin "A1") (pinfunction "~{INT}_A1") (pintype "bidirectional"))
      (node (ref "U1") (pin "P$T2") (pinfunction "P0.11_P$T2") (pintype "bidirectional"))
    )
    (net (code "104") (name "PREVGH") (class "Default")
      (node (ref "D5") (pin "1") (pinfunction "K_1") (pintype "bidirectional"))
      (node (ref "EPD_C9") (pin "2") (pinfunction "2_2") (pintype "passive"))
      (node (ref "J1") (pin "21") (pinfunction "21_21") (pintype "bidirectional"))
    )
    (net (code "105") (name "PREVGL") (class "Default")
      (node (ref "D2") (pin "2") (pinfunction "A_2") (pintype "bidirectional"))
      (node (ref "EPD_C11") (pin "2") (pinfunction "2_2") (pintype "passive"))
      (node (ref "J1") (pin "23") (pinfunction "23_23") (pintype "bidirectional"))
    )
    (net (code "106") (name "RESE") (class "Default")
      (node (ref "J1") (pin "3") (pinfunction "3_3") (pintype "bidirectional"))
      (node (ref "Q3") (pin "2") (pinfunction "S_2") (pintype "bidirectional"))
      (node (ref "R1_EP_DR") (pin "2") (pinfunction "2_2") (pintype "bidirectional"))
    )
    (net (code "107") (name "RESET") (class "Default")
      (node (ref "J2") (pin "6") (pinfunction "6_6") (pintype "bidirectional"))
      (node (ref "TP_RESET") (pin "TP") (pinfunction "TP_TP") (pintype "input"))
      (node (ref "U1") (pin "P$AC13") (pinfunction "P0.18/RESET_P$AC13") (pintype "bidirectional"))
    )
    (net (code "108") (name "SCK{slash}1.5B") (class "Default")
      (node (ref "J1") (pin "13") (pinfunction "13_13") (pintype "bidirectional"))
    )
    (net (code "109") (name "SCK{slash}2.2D") (class "Default")
      (node (ref "U1") (pin "P$A12") (pinfunction "P0.02/AIN0_P$A12") (pintype "bidirectional"))
    )
    (net (code "110") (name "SCL{slash}1.4C") (class "Default")
      (node (ref "IC2") (pin "C1") (pinfunction "SCL_C1") (pintype "bidirectional"))
      (node (ref "U3") (pin "7") (pinfunction "SCL_7") (pintype "input"))
    )
    (net (code "111") (name "SCL{slash}2.4C") (class "Default")
      (node (ref "IC1") (pin "B1") (pinfunction "SCL_B1") (pintype "bidirectional"))
      (node (ref "IC3") (pin "12") (pinfunction "SCX_12") (pintype "bidirectional"))
      (node (ref "R17") (pin "2") (pinfunction "2_2") (pintype "bidirectional"))
      (node (ref "R4") (pin "1") (pinfunction "1_1") (pintype "bidirectional"))
      (node (ref "TP_SCL") (pin "TP") (pinfunction "TP_TP") (pintype "input"))
      (node (ref "U1") (pin "P$M2") (pinfunction "P0.07_P$M2") (pintype "bidirectional"))
    )
    (net (code "112") (name "SDA{slash}1.4C") (class "Default")
      (node (ref "IC2") (pin "B2") (pinfunction "SDA_B2") (pintype "bidirectional"))
      (node (ref "U3") (pin "8") (pinfunction "SDA_8") (pintype "bidirectional"))
    )
    (net (code "113") (name "SDA{slash}2.4C") (class "Default")
      (node (ref "IC1") (pin "C1") (pinfunction "SDA_C1") (pintype "bidirectional"))
      (node (ref "IC3") (pin "2") (pinfunction "SDX_2") (pintype "bidirectional"))
      (node (ref "R18") (pin "2") (pinfunction "2_2") (pintype "bidirectional"))
      (node (ref "R2") (pin "1") (pinfunction "1_1") (pintype "bidirectional"))
      (node (ref "TP_SDA") (pin "TP") (pinfunction "TP_TP") (pintype "input"))
      (node (ref "U1") (pin "P$L1") (pinfunction "P0.06_P$L1") (pintype "bidirectional"))
    )
    (net (code "114") (name "SWDCLK") (class "Default")
      (node (ref "J2") (pin "4") (pinfunction "4_4") (pintype "bidirectional"))
      (node (ref "TP_SWDCLK") (pin "TP") (pinfunction "TP_TP") (pintype "input"))
      (node (ref "U1") (pin "P$AA24") (pinfunction "SWDCLK_P$AA24") (pintype "input"))
    )
    (net (code "115") (name "SWDIO") (class "Default")
      (node (ref "J2") (pin "2") (pinfunction "2_2") (pintype "bidirectional"))
      (node (ref "TP_SWDIO") (pin "TP") (pinfunction "TP_TP") (pintype "input"))
      (node (ref "U1") (pin "P$AC24") (pinfunction "SWDIO_P$AC24") (pintype "bidirectional"))
    )
    (net (code "116") (name "SWO") (class "Default")
      (node (ref "TP_SWO") (pin "TP") (pinfunction "TP_TP") (pintype "input"))
      (node (ref "U1") (pin "P$AD22") (pinfunction "P1.00_P$AD22") (pintype "bidirectional"))
    )
    (net (code "117") (name "VBAT{slash}1.2A") (class "Default")
      (node (ref "C27") (pin "2") (pinfunction "2_2") (pintype "passive"))
      (node (ref "TP_VBAT") (pin "TP") (pinfunction "TP_TP") (pintype "input"))
      (node (ref "U3") (pin "2") (pinfunction "CELL_2") (pintype "power_in"))
      (node (ref "U3") (pin "3") (pinfunction "VDD_3") (pintype "power_in"))
    )
    (net (code "118") (name "VBAT{slash}2.5C") (class "Default")
      (node (ref "C37") (pin "2") (pinfunction "2_2") (pintype "passive"))
      (node (ref "IC1") (pin "C2") (pinfunction "BAT_C2") (pintype "bidirectional"))
    )
    (net (code "119") (name "VBUS{slash}1.5D") (class "Default")
      (node (ref "C42") (pin "1") (pinfunction "1_1") (pintype "passive"))
      (node (ref "C43") (pin "1") (pinfunction "1_1") (pintype "passive"))
      (node (ref "D3") (pin "5") (pinfunction "VBUS_5") (pintype "bidirectional"))
      (node (ref "J4") (pin "A4_B9") (pinfunction "VBUS_A4_B9") (pintype "power_in"))
      (node (ref "J4") (pin "A9_B4") (pinfunction "VBUS_A9_B4") (pintype "power_in"))
    )
    (net (code "120") (name "VBUS{slash}2.6D") (class "Default")
      (node (ref "C21") (pin "1") (pinfunction "1_1") (pintype "passive"))
      (node (ref "C38") (pin "2") (pinfunction "2_2") (pintype "passive"))
      (node (ref "IC1") (pin "A2") (pinfunction "IN_A2") (pintype "bidirectional"))
      (node (ref "U1") (pin "P$AD2") (pinfunction "VBUS_P$AD2") (pintype "power_in"))
    )
    (net (code "121") (name "VREG") (class "Default")
      (node (ref "C23") (pin "1") (pinfunction "1_1") (pintype "passive"))
      (node (ref "C24") (pin "2") (pinfunction "2_2") (pintype "passive"))
      (node (ref "C39") (pin "1") (pinfunction "1_1") (pintype "passive"))
      (node (ref "IC1") (pin "B2") (pinfunction "SYS_B2") (pintype "bidirectional"))
      (node (ref "IC9") (pin "A1") (pinfunction "EN_A1") (pintype "bidirectional"))
      (node (ref "IC9") (pin "A2") (pinfunction "VIN_1_A2") (pintype "bidirectional"))
      (node (ref "IC9") (pin "A3") (pinfunction "VIN_2_A3") (pintype "bidirectional"))
      (node (ref "TP_VREG") (pin "TP") (pinfunction "TP_TP") (pintype "input"))
    )
    (net (code "122") (name "unconnected-(ANT1-NC-Pad2)") (class "Default")
      (node (ref "ANT1") (pin "2") (pinfunction "NC_2") (pintype "no_connect"))
    )
    (net (code "123") (name "unconnected-(C27-Pad1)") (class "Default")
      (node (ref "C27") (pin "1") (pinfunction "1_1") (pintype "passive"))
    )
    (net (code "124") (name "unconnected-(EPD_C1-Pad1)") (class "Default")
      (node (ref "EPD_C1") (pin "1") (pinfunction "1_1") (pintype "passive"))
    )
    (net (code "125") (name "unconnected-(EPD_C2-Pad1)") (class "Default")
      (node (ref "EPD_C2") (pin "1") (pinfunction "1_1") (pintype "passive"))
    )
    (net (code "126") (name "unconnected-(IC3-ASCL-Pad11)") (class "Default")
      (node (ref "IC3") (pin "11") (pinfunction "ASCL_11") (pintype "bidirectional"))
    )
    (net (code "127") (name "unconnected-(IC3-ASDA-Pad4)") (class "Default")
      (node (ref "IC3") (pin "4") (pinfunction "ASDA_4") (pintype "bidirectional"))
    )
    (net (code "128") (name "unconnected-(J1-Pad1)") (class "Default")
      (node (ref "J1") (pin "1") (pinfunction "1_1") (pintype "bidirectional"))
    )
    (net (code "129") (name "unconnected-(J1-Pad6)") (class "Default")
      (node (ref "J1") (pin "6") (pinfunction "6_6") (pintype "bidirectional"))
    )
    (net (code "130") (name "unconnected-(J1-Pad7)") (class "Default")
      (node (ref "J1") (pin "7") (pinfunction "7_7") (pintype "bidirectional"))
    )
    (net (code "131") (name "unconnected-(J1-PadMP2)") (class "Default")
      (node (ref "J1") (pin "MP2") (pinfunction "MP2_MP2") (pintype "bidirectional"))
    )
    (net (code "132") (name "unconnected-(J4-SBU1-PadA8)") (class "Default")
      (node (ref "J4") (pin "A8") (pinfunction "SBU1_A8") (pintype "bidirectional"))
    )
    (net (code "133") (name "unconnected-(J4-SBU2-PadB8)") (class "Default")
      (node (ref "J4") (pin "B8") (pinfunction "SBU2_B8") (pintype "bidirectional"))
    )
    (net (code "134") (name "unconnected-(U1-DCCH-PadP$AB2)") (class "Default")
      (node (ref "U1") (pin "P$AB2") (pinfunction "DCCH_P$AB2") (pintype "bidirectional"))
    )
  )
)
